# circuit.net
KiCad netlist of a schematic drawn in EAGLE
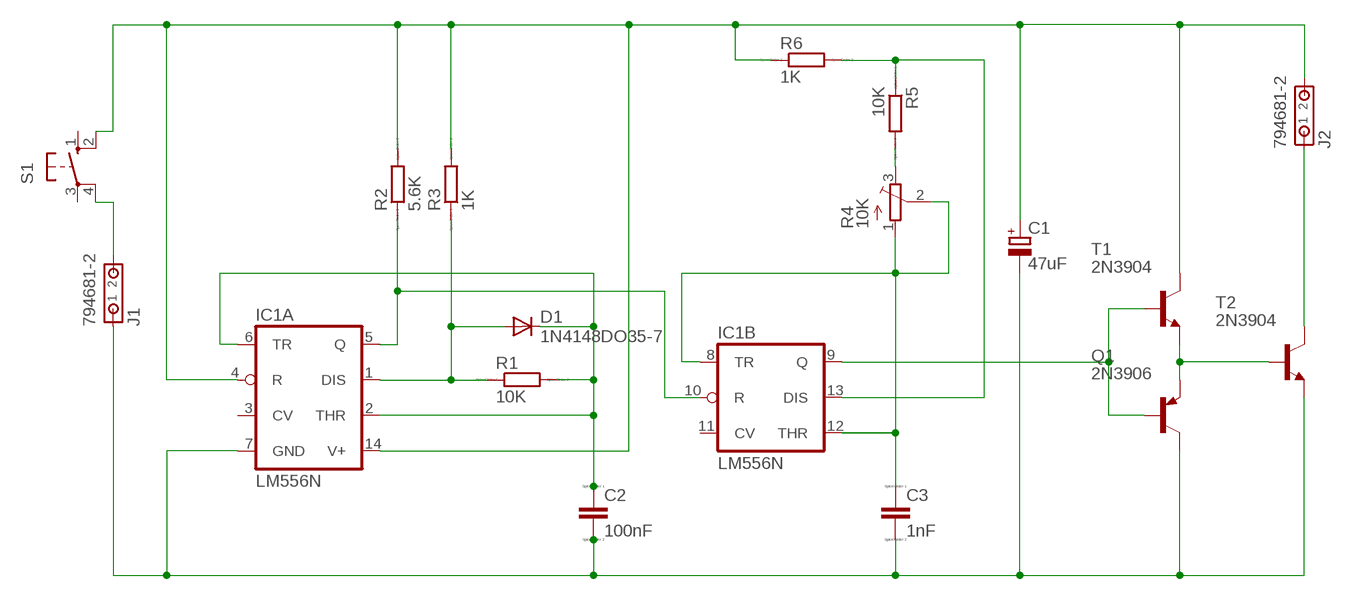
[diagram p0: schematic, sheet 1]

(export (version "E")
  (design (tool "Eeschema 10.0.6"))
  (components
    (comp (ref "C1")
      (value "47uF")
      (footprint "eagle-import:B45181B")
      (libsource (lib "eagle-import") (part "CPOL-EUB45181B"))
    )
    (comp (ref "C2")
      (value "100nF")
      (footprint "eagle-import:C0805")
      (libsource (lib "eagle-import") (part "C"))
    )
    (comp (ref "C3")
      (value "1nF")
      (footprint "eagle-import:C0805")
      (libsource (lib "eagle-import") (part "C"))
    )
    (comp (ref "D1")
      (value "1N4148DO35-7")
      (footprint "eagle-import:DO35-7")
      (libsource (lib "eagle-import") (part "1N4148DO35-7"))
    )
    (comp (ref "IC1")
      (value "LM556N")
      (footprint "eagle-import:DIL14")
      (libsource (lib "eagle-import") (part "556NLM"))
    )
    (comp (ref "J1")
      (value "794681-2")
      (footprint "eagle-import:794681-2")
      (libsource (lib "eagle-import") (part "794681-2"))
    )
    (comp (ref "J2")
      (value "794681-2")
      (footprint "eagle-import:794681-2")
      (libsource (lib "eagle-import") (part "794681-2"))
    )
    (comp (ref "Q1")
      (value "2N3906")
      (footprint "eagle-import:TO92")
      (libsource (lib "eagle-import") (part "2N3906"))
    )
    (comp (ref "R1")
      (value "10K")
      (footprint "eagle-import:R0805")
      (libsource (lib "eagle-import") (part "R"))
    )
    (comp (ref "R2")
      (value "5.6K")
      (footprint "eagle-import:R0805")
      (libsource (lib "eagle-import") (part "R"))
    )
    (comp (ref "R3")
      (value "1K")
      (footprint "eagle-import:R0805")
      (libsource (lib "eagle-import") (part "R"))
    )
    (comp (ref "R4")
      (value "10K")
      (footprint "eagle-import:3223J")
      (libsource (lib "eagle-import") (part "TRIM_EU-3223J"))
    )
    (comp (ref "R5")
      (value "10K")
      (footprint "eagle-import:R0805")
      (libsource (lib "eagle-import") (part "R"))
    )
    (comp (ref "R6")
      (value "1K")
      (footprint "eagle-import:R0805")
      (libsource (lib "eagle-import") (part "R"))
    )
    (comp (ref "S1")
      (value "10-XX")
      (footprint "eagle-import:B3F-10XX")
      (fields (field (name "MPN") "B3F-1000"))
      (libsource (lib "eagle-import") (part "10-XX"))
    )
    (comp (ref "T1")
      (value "2N3904")
      (footprint "eagle-import:TO92")
      (libsource (lib "eagle-import") (part "2N3904"))
    )
    (comp (ref "T2")
      (value "2N3904")
      (footprint "eagle-import:TO92")
      (libsource (lib "eagle-import") (part "2N3904"))
    )
  )
  (nets
    (net (code "1") (name "Net-(IC1A-DIS)") (class "Default")
      (node (ref "D1") (pin "A") (pinfunction "A_A") (pintype "passive"))
      (node (ref "IC1") (pin "1") (pinfunction "DIS_1") (pintype "input"))
      (node (ref "R1") (pin "1") (pinfunction "1_1") (pintype "passive"))
      (node (ref "R3") (pin "1") (pinfunction "1_1") (pintype "passive"))
    )
    (net (code "2") (name "Net-(IC1A-GND)") (class "Default")
      (node (ref "C1") (pin "-") (pinfunction "-_-") (pintype "passive"))
      (node (ref "C2") (pin "2") (pinfunction "2_2") (pintype "passive"))
      (node (ref "C3") (pin "2") (pinfunction "2_2") (pintype "passive"))
      (node (ref "IC1") (pin "7") (pinfunction "GND_7") (pintype "power_in"))
      (node (ref "J1") (pin "1") (pinfunction "1_1") (pintype "passive"))
      (node (ref "Q1") (pin "1") (pinfunction "C_1") (pintype "passive"))
      (node (ref "T2") (pin "3") (pinfunction "E_3") (pintype "passive"))
    )
    (net (code "3") (name "Net-(IC1A-Q)") (class "Default")
      (node (ref "IC1") (pin "10") (pinfunction "R_10") (pintype "input"))
      (node (ref "IC1") (pin "5") (pinfunction "Q_5") (pintype "output"))
      (node (ref "R2") (pin "1") (pinfunction "1_1") (pintype "passive"))
    )
    (net (code "4") (name "Net-(IC1A-R)") (class "Default")
      (node (ref "C1") (pin "+") (pinfunction "+_+") (pintype "passive"))
      (node (ref "IC1") (pin "14") (pinfunction "V+_14") (pintype "power_in"))
      (node (ref "IC1") (pin "4") (pinfunction "R_4") (pintype "input"))
      (node (ref "J2") (pin "2") (pinfunction "2_2") (pintype "passive"))
      (node (ref "R2") (pin "2") (pinfunction "2_2") (pintype "passive"))
      (node (ref "R3") (pin "2") (pinfunction "2_2") (pintype "passive"))
      (node (ref "R6") (pin "1") (pinfunction "1_1") (pintype "passive"))
      (node (ref "S1") (pin "2") (pinfunction "S1_2") (pintype "passive"))
      (node (ref "T1") (pin "1") (pinfunction "C_1") (pintype "passive"))
    )
    (net (code "5") (name "Net-(IC1A-THR)") (class "Default")
      (node (ref "C2") (pin "1") (pinfunction "1_1") (pintype "passive"))
      (node (ref "D1") (pin "C") (pinfunction "C_C") (pintype "passive"))
      (node (ref "IC1") (pin "2") (pinfunction "THR_2") (pintype "input"))
      (node (ref "IC1") (pin "6") (pinfunction "TR_6") (pintype "input"))
      (node (ref "R1") (pin "2") (pinfunction "2_2") (pintype "passive"))
    )
    (net (code "6") (name "Net-(IC1B-DIS)") (class "Default")
      (node (ref "IC1") (pin "13") (pinfunction "DIS_13") (pintype "input"))
      (node (ref "R5") (pin "1") (pinfunction "1_1") (pintype "passive"))
      (node (ref "R6") (pin "2") (pinfunction "2_2") (pintype "passive"))
    )
    (net (code "7") (name "Net-(IC1B-Q)") (class "Default")
      (node (ref "IC1") (pin "9") (pinfunction "Q_9") (pintype "output"))
      (node (ref "Q1") (pin "2") (pinfunction "B_2") (pintype "passive"))
      (node (ref "T1") (pin "2") (pinfunction "B_2") (pintype "passive"))
    )
    (net (code "8") (name "Net-(IC1B-THR)") (class "Default")
      (node (ref "C3") (pin "1") (pinfunction "1_1") (pintype "passive"))
      (node (ref "IC1") (pin "12") (pinfunction "THR_12") (pintype "input"))
      (node (ref "IC1") (pin "8") (pinfunction "TR_8") (pintype "input"))
      (node (ref "R4") (pin "1") (pinfunction "A_1") (pintype "passive"))
      (node (ref "R4") (pin "2") (pinfunction "S_2") (pintype "passive"))
    )
    (net (code "9") (name "Net-(Q1-E)") (class "Default")
      (node (ref "Q1") (pin "3") (pinfunction "E_3") (pintype "passive"))
      (node (ref "T1") (pin "3") (pinfunction "E_3") (pintype "passive"))
      (node (ref "T2") (pin "2") (pinfunction "B_2") (pintype "passive"))
    )
    (net (code "10") (name "Net-(R4-E)") (class "Default")
      (node (ref "R4") (pin "3") (pinfunction "E_3") (pintype "passive"))
      (node (ref "R5") (pin "2") (pinfunction "2_2") (pintype "passive"))
    )
    (net (code "11") (name "Net-(S1-P1)") (class "Default")
      (node (ref "J1") (pin "2") (pinfunction "2_2") (pintype "passive"))
      (node (ref "S1") (pin "4") (pinfunction "P1_4") (pintype "passive"))
    )
    (net (code "12") (name "Net-(T2-C)") (class "Default")
      (node (ref "J2") (pin "1") (pinfunction "1_1") (pintype "passive"))
      (node (ref "T2") (pin "1") (pinfunction "C_1") (pintype "passive"))
    )
    (net (code "13") (name "unconnected-(IC1A-CV-Pad3)") (class "Default")
      (node (ref "IC1") (pin "3") (pinfunction "CV_3") (pintype "input"))
    )
    (net (code "14") (name "unconnected-(IC1B-CV-Pad11)") (class "Default")
      (node (ref "IC1") (pin "11") (pinfunction "CV_11") (pintype "input"))
    )
    (net (code "15") (name "unconnected-(S1-P-Pad3)") (class "Default")
      (node (ref "S1") (pin "3") (pinfunction "P_3") (pintype "passive"))
    )
    (net (code "16") (name "unconnected-(S1-S-Pad1)") (class "Default")
      (node (ref "S1") (pin "1") (pinfunction "S_1") (pintype "passive"))
    )
  )
)
